# CM_CLK.net
KiCad netlist of a schematic drawn in Altium Designer
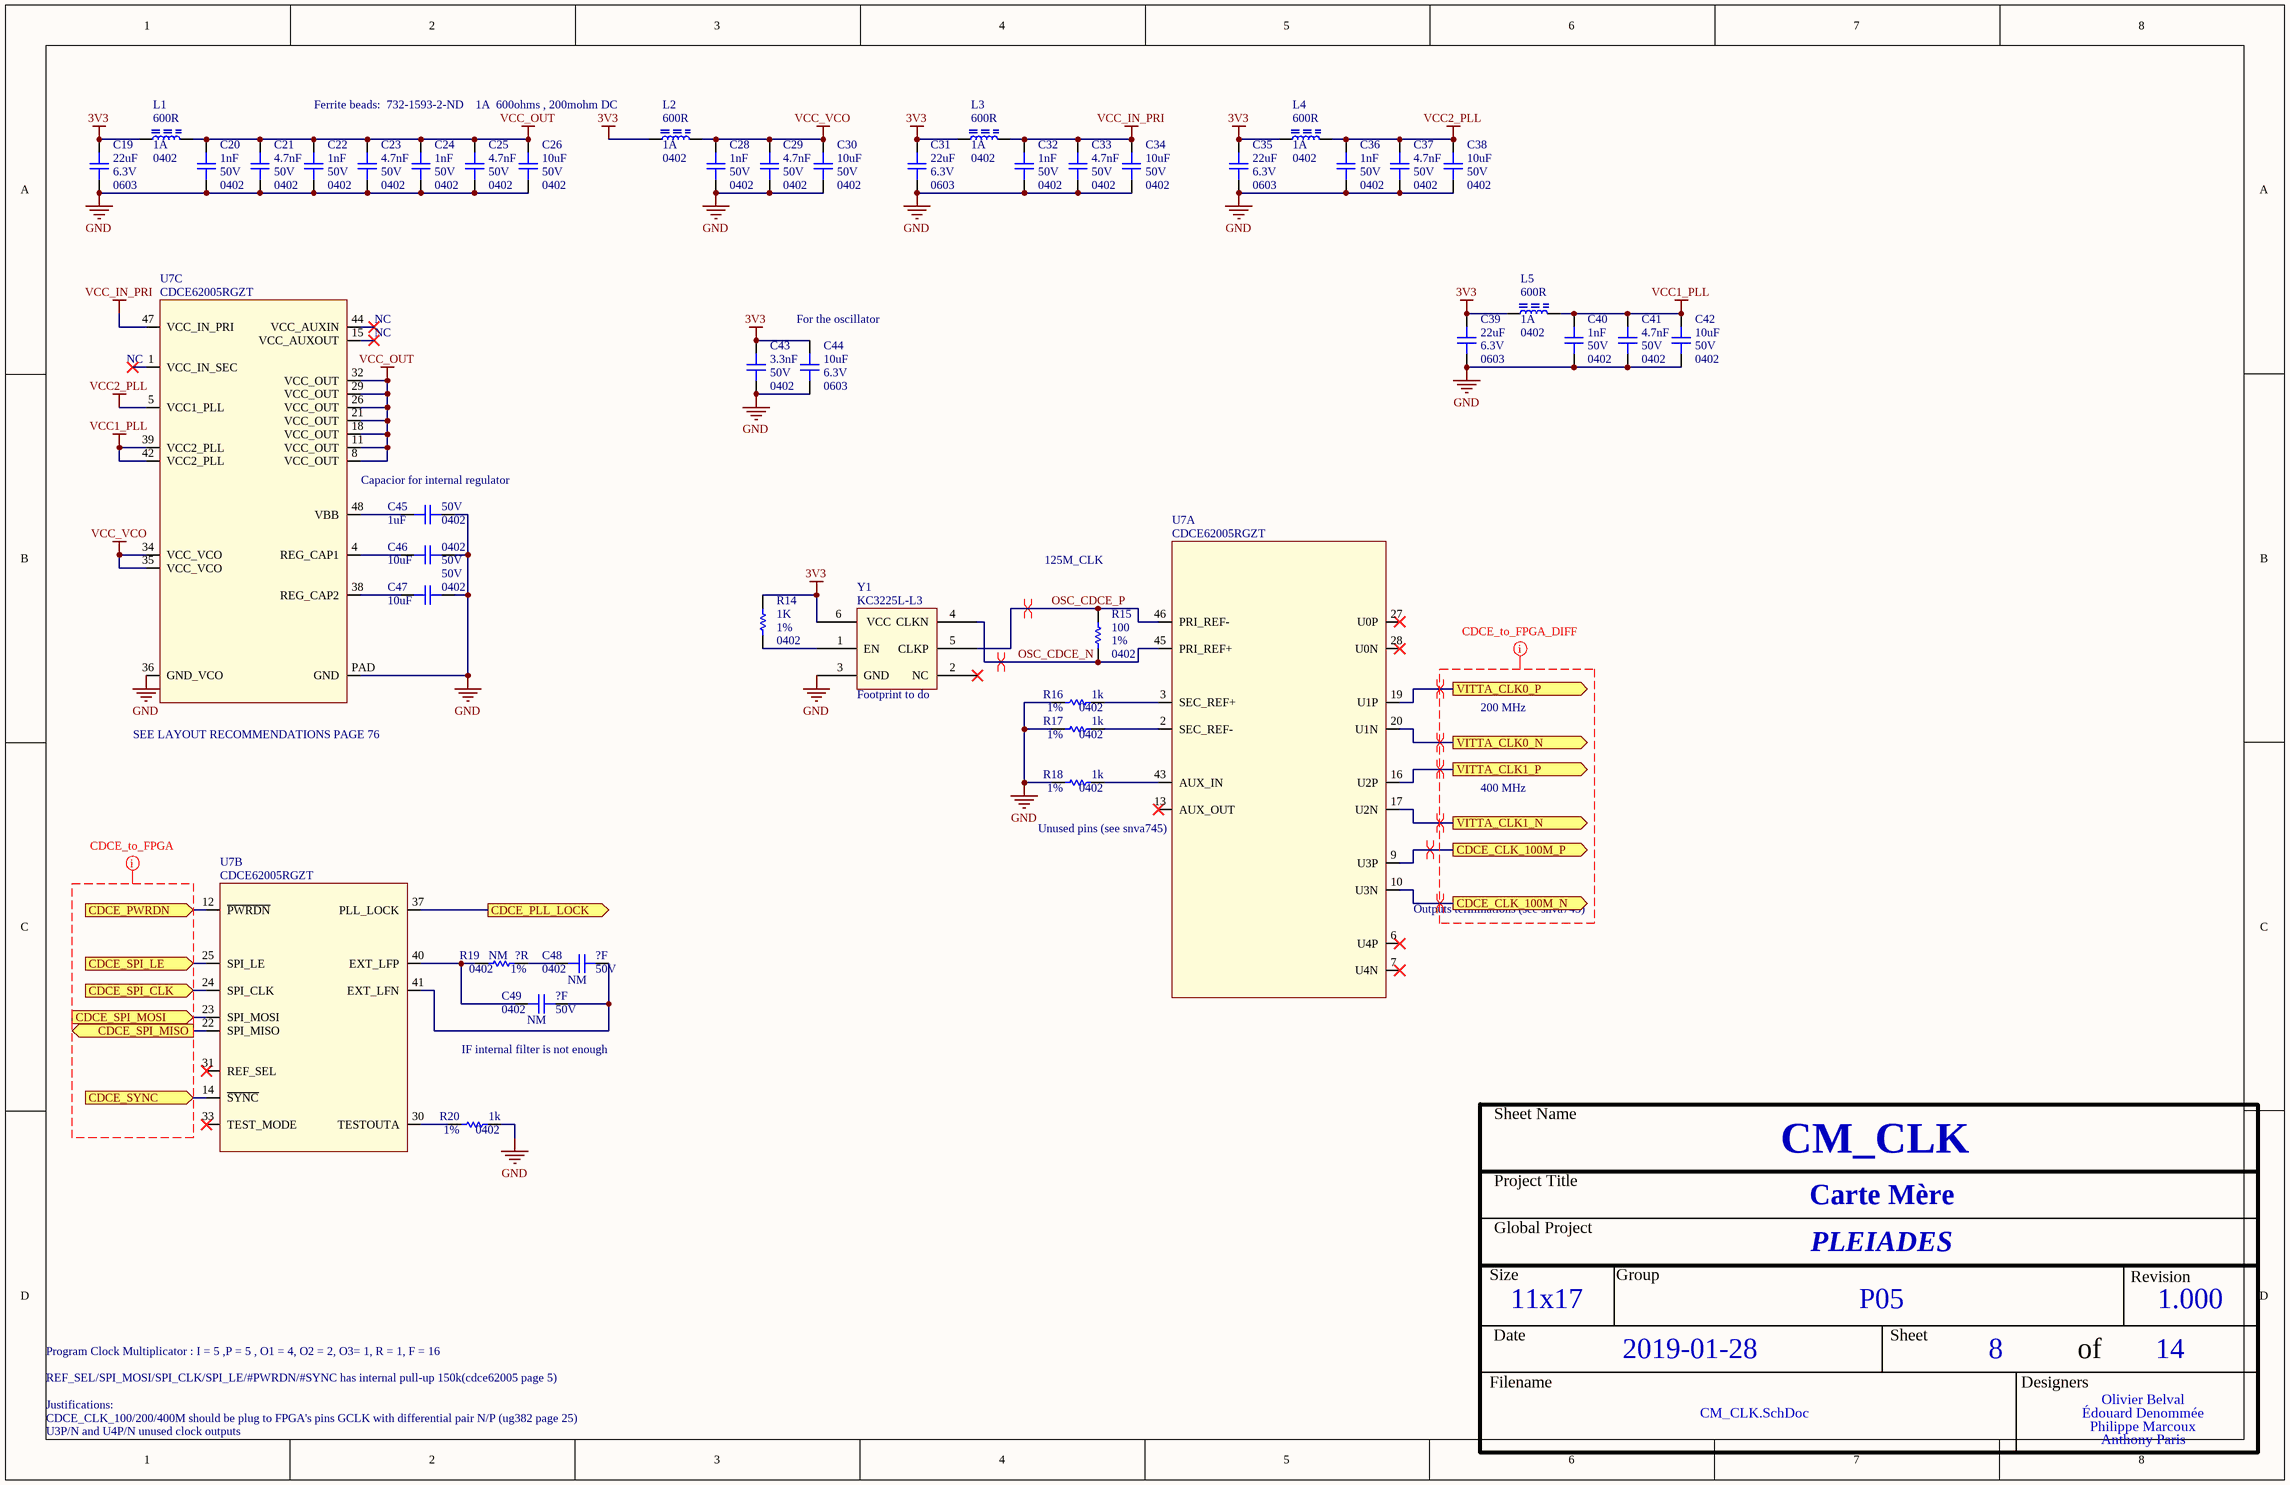
[diagram p0: CM_CLK.SchDoc]

(export (version "E")
  (design (tool "Eeschema 10.0.6"))
  (components
    (comp (ref "C19")
      (value "22uF")
      (footprint "CAP_0603")
      (description "CAP - 0603")
      (fields
        (field (name "VOLTAGE") "6.3V")
        (field (name "PACKAGE") "0603")
        (field (name "CREATEDBY") "Jonathan Bouchard")
      )
      (libsource (lib "S7CAS_Lib2019_REV1_00") (part "CAP - 0603"))
    )
    (comp (ref "C20")
      (value "1nF")
      (footprint "CAP_0402")
      (description "CAP - 0402")
      (fields
        (field (name "VOLTAGE") "50V")
        (field (name "PACKAGE") "0402")
        (field (name "CREATEDBY") "Jonathan Bouchard")
      )
      (libsource (lib "S7CAS_Lib2019_REV1_00") (part "CAP - 0402"))
    )
    (comp (ref "C21")
      (value "4.7nF")
      (footprint "CAP_0402")
      (description "CAP - 0402")
      (fields
        (field (name "VOLTAGE") "50V")
        (field (name "PACKAGE") "0402")
        (field (name "CREATEDBY") "Jonathan Bouchard")
      )
      (libsource (lib "S7CAS_Lib2019_REV1_00") (part "CAP - 0402"))
    )
    (comp (ref "C22")
      (value "1nF")
      (footprint "CAP_0402")
      (description "CAP - 0402")
      (fields
        (field (name "VOLTAGE") "50V")
        (field (name "PACKAGE") "0402")
        (field (name "CREATEDBY") "Jonathan Bouchard")
      )
      (libsource (lib "S7CAS_Lib2019_REV1_00") (part "CAP - 0402"))
    )
    (comp (ref "C23")
      (value "4.7nF")
      (footprint "CAP_0402")
      (description "CAP - 0402")
      (fields
        (field (name "VOLTAGE") "50V")
        (field (name "PACKAGE") "0402")
        (field (name "CREATEDBY") "Jonathan Bouchard")
      )
      (libsource (lib "S7CAS_Lib2019_REV1_00") (part "CAP - 0402"))
    )
    (comp (ref "C24")
      (value "1nF")
      (footprint "CAP_0402")
      (description "CAP - 0402")
      (fields
        (field (name "VOLTAGE") "50V")
        (field (name "PACKAGE") "0402")
        (field (name "CREATEDBY") "Jonathan Bouchard")
      )
      (libsource (lib "S7CAS_Lib2019_REV1_00") (part "CAP - 0402"))
    )
    (comp (ref "C25")
      (value "4.7nF")
      (footprint "CAP_0402")
      (description "CAP - 0402")
      (fields
        (field (name "VOLTAGE") "50V")
        (field (name "PACKAGE") "0402")
        (field (name "CREATEDBY") "Jonathan Bouchard")
      )
      (libsource (lib "S7CAS_Lib2019_REV1_00") (part "CAP - 0402"))
    )
    (comp (ref "C26")
      (value "10uF")
      (footprint "CAP_0402")
      (description "CAP - 0402")
      (fields
        (field (name "VOLTAGE") "50V")
        (field (name "PACKAGE") "0402")
        (field (name "CREATEDBY") "Jonathan Bouchard")
      )
      (libsource (lib "S7CAS_Lib2019_REV1_00") (part "CAP - 0402"))
    )
    (comp (ref "C28")
      (value "1nF")
      (footprint "CAP_0402")
      (description "CAP - 0402")
      (fields
        (field (name "VOLTAGE") "50V")
        (field (name "PACKAGE") "0402")
        (field (name "CREATEDBY") "Jonathan Bouchard")
      )
      (libsource (lib "S7CAS_Lib2019_REV1_00") (part "CAP - 0402"))
    )
    (comp (ref "C29")
      (value "4.7nF")
      (footprint "CAP_0402")
      (description "CAP - 0402")
      (fields
        (field (name "VOLTAGE") "50V")
        (field (name "PACKAGE") "0402")
        (field (name "CREATEDBY") "Jonathan Bouchard")
      )
      (libsource (lib "S7CAS_Lib2019_REV1_00") (part "CAP - 0402"))
    )
    (comp (ref "C30")
      (value "10uF")
      (footprint "CAP_0402")
      (description "CAP - 0402")
      (fields
        (field (name "VOLTAGE") "50V")
        (field (name "PACKAGE") "0402")
        (field (name "CREATEDBY") "Jonathan Bouchard")
      )
      (libsource (lib "S7CAS_Lib2019_REV1_00") (part "CAP - 0402"))
    )
    (comp (ref "C31")
      (value "22uF")
      (footprint "CAP_0603")
      (description "CAP - 0603")
      (fields
        (field (name "VOLTAGE") "6.3V")
        (field (name "PACKAGE") "0603")
        (field (name "CREATEDBY") "Jonathan Bouchard")
      )
      (libsource (lib "S7CAS_Lib2019_REV1_00") (part "CAP - 0603"))
    )
    (comp (ref "C32")
      (value "1nF")
      (footprint "CAP_0402")
      (description "CAP - 0402")
      (fields
        (field (name "VOLTAGE") "50V")
        (field (name "PACKAGE") "0402")
        (field (name "CREATEDBY") "Jonathan Bouchard")
      )
      (libsource (lib "S7CAS_Lib2019_REV1_00") (part "CAP - 0402"))
    )
    (comp (ref "C33")
      (value "4.7nF")
      (footprint "CAP_0402")
      (description "CAP - 0402")
      (fields
        (field (name "VOLTAGE") "50V")
        (field (name "PACKAGE") "0402")
        (field (name "CREATEDBY") "Jonathan Bouchard")
      )
      (libsource (lib "S7CAS_Lib2019_REV1_00") (part "CAP - 0402"))
    )
    (comp (ref "C34")
      (value "10uF")
      (footprint "CAP_0402")
      (description "CAP - 0402")
      (fields
        (field (name "VOLTAGE") "50V")
        (field (name "PACKAGE") "0402")
        (field (name "CREATEDBY") "Jonathan Bouchard")
      )
      (libsource (lib "S7CAS_Lib2019_REV1_00") (part "CAP - 0402"))
    )
    (comp (ref "C35")
      (value "22uF")
      (footprint "CAP_0603")
      (description "CAP - 0603")
      (fields
        (field (name "VOLTAGE") "6.3V")
        (field (name "PACKAGE") "0603")
        (field (name "CREATEDBY") "Jonathan Bouchard")
      )
      (libsource (lib "S7CAS_Lib2019_REV1_00") (part "CAP - 0603"))
    )
    (comp (ref "C36")
      (value "1nF")
      (footprint "CAP_0402")
      (description "CAP - 0402")
      (fields
        (field (name "VOLTAGE") "50V")
        (field (name "PACKAGE") "0402")
        (field (name "CREATEDBY") "Jonathan Bouchard")
      )
      (libsource (lib "S7CAS_Lib2019_REV1_00") (part "CAP - 0402"))
    )
    (comp (ref "C37")
      (value "4.7nF")
      (footprint "CAP_0402")
      (description "CAP - 0402")
      (fields
        (field (name "VOLTAGE") "50V")
        (field (name "PACKAGE") "0402")
        (field (name "CREATEDBY") "Jonathan Bouchard")
      )
      (libsource (lib "S7CAS_Lib2019_REV1_00") (part "CAP - 0402"))
    )
    (comp (ref "C38")
      (value "10uF")
      (footprint "CAP_0402")
      (description "CAP - 0402")
      (fields
        (field (name "VOLTAGE") "50V")
        (field (name "PACKAGE") "0402")
        (field (name "CREATEDBY") "Jonathan Bouchard")
      )
      (libsource (lib "S7CAS_Lib2019_REV1_00") (part "CAP - 0402"))
    )
    (comp (ref "C39")
      (value "22uF")
      (footprint "CAP_0603")
      (description "CAP - 0603")
      (fields
        (field (name "VOLTAGE") "6.3V")
        (field (name "PACKAGE") "0603")
        (field (name "CREATEDBY") "Jonathan Bouchard")
      )
      (libsource (lib "S7CAS_Lib2019_REV1_00") (part "CAP - 0603"))
    )
    (comp (ref "C40")
      (value "1nF")
      (footprint "CAP_0402")
      (description "CAP - 0402")
      (fields
        (field (name "VOLTAGE") "50V")
        (field (name "PACKAGE") "0402")
        (field (name "CREATEDBY") "Jonathan Bouchard")
      )
      (libsource (lib "S7CAS_Lib2019_REV1_00") (part "CAP - 0402"))
    )
    (comp (ref "C41")
      (value "4.7nF")
      (footprint "CAP_0402")
      (description "CAP - 0402")
      (fields
        (field (name "VOLTAGE") "50V")
        (field (name "PACKAGE") "0402")
        (field (name "CREATEDBY") "Jonathan Bouchard")
      )
      (libsource (lib "S7CAS_Lib2019_REV1_00") (part "CAP - 0402"))
    )
    (comp (ref "C42")
      (value "10uF")
      (footprint "CAP_0402")
      (description "CAP - 0402")
      (fields
        (field (name "VOLTAGE") "50V")
        (field (name "PACKAGE") "0402")
        (field (name "CREATEDBY") "Jonathan Bouchard")
      )
      (libsource (lib "S7CAS_Lib2019_REV1_00") (part "CAP - 0402"))
    )
    (comp (ref "C43")
      (value "3.3nF")
      (footprint "CAP_0402")
      (description "CAP - 0402")
      (fields
        (field (name "VOLTAGE") "50V")
        (field (name "PACKAGE") "0402")
        (field (name "CREATEDBY") "Jonathan Bouchard")
      )
      (libsource (lib "S7CAS_Lib2019_REV1_00") (part "CAP - 0402"))
    )
    (comp (ref "C44")
      (value "10uF")
      (footprint "CAP_0603")
      (description "CAP - 0603")
      (fields
        (field (name "VOLTAGE") "6.3V")
        (field (name "PACKAGE") "0603")
        (field (name "CREATEDBY") "Jonathan Bouchard")
      )
      (libsource (lib "S7CAS_Lib2019_REV1_00") (part "CAP - 0603"))
    )
    (comp (ref "C45")
      (value "1uF")
      (footprint "CAP_0402")
      (description "CAP - 0402")
      (fields
        (field (name "VOLTAGE") "50V")
        (field (name "PACKAGE") "0402")
        (field (name "CREATEDBY") "Jonathan Bouchard")
      )
      (libsource (lib "S7CAS_Lib2019_REV1_00") (part "CAP - 0402"))
    )
    (comp (ref "C46")
      (value "10uF")
      (footprint "CAP_0402")
      (description "CAP - 0402")
      (fields
        (field (name "VOLTAGE") "50V")
        (field (name "PACKAGE") "0402")
        (field (name "CREATEDBY") "Jonathan Bouchard")
      )
      (libsource (lib "S7CAS_Lib2019_REV1_00") (part "CAP - 0402"))
    )
    (comp (ref "C47")
      (value "10uF")
      (footprint "CAP_0402")
      (description "CAP - 0402")
      (fields
        (field (name "VOLTAGE") "50V")
        (field (name "PACKAGE") "0402")
        (field (name "CREATEDBY") "Jonathan Bouchard")
      )
      (libsource (lib "S7CAS_Lib2019_REV1_00") (part "CAP - 0402"))
    )
    (comp (ref "C48")
      (value "NM")
      (footprint "CAP_0402")
      (description "CAP - 0402")
      (fields
        (field (name "VOLTAGE") "50V")
        (field (name "PACKAGE") "0402")
        (field (name "ALTIUM_VALUE") "?F")
        (field (name "CREATEDBY") "Jonathan Bouchard")
      )
      (libsource (lib "S7CAS_Lib2019_REV1_00") (part "CAP - 0402"))
    )
    (comp (ref "C49")
      (value "NM")
      (footprint "CAP_0402")
      (description "CAP - 0402")
      (fields
        (field (name "VOLTAGE") "50V")
        (field (name "PACKAGE") "0402")
        (field (name "ALTIUM_VALUE") "?F")
        (field (name "CREATEDBY") "Jonathan Bouchard")
      )
      (libsource (lib "S7CAS_Lib2019_REV1_00") (part "CAP - 0402"))
    )
    (comp (ref "L1")
      (value "600R")
      (footprint "FER_0402")
      (description "FER - 0402")
      (fields
        (field (name "CURRENT") "1A")
        (field (name "PACKAGE") "0402")
        (field (name "CREATEDBY") "Jonathan Bouchard")
      )
      (libsource (lib "S7CAS_Lib2019_REV1_00") (part "FER - 0402"))
    )
    (comp (ref "L2")
      (value "600R")
      (footprint "FER_0402")
      (description "FER - 0402")
      (fields
        (field (name "CURRENT") "1A")
        (field (name "PACKAGE") "0402")
        (field (name "CREATEDBY") "Jonathan Bouchard")
      )
      (libsource (lib "S7CAS_Lib2019_REV1_00") (part "FER - 0402"))
    )
    (comp (ref "L3")
      (value "600R")
      (footprint "FER_0402")
      (description "FER - 0402")
      (fields
        (field (name "CURRENT") "1A")
        (field (name "PACKAGE") "0402")
        (field (name "CREATEDBY") "Jonathan Bouchard")
      )
      (libsource (lib "S7CAS_Lib2019_REV1_00") (part "FER - 0402"))
    )
    (comp (ref "L4")
      (value "600R")
      (footprint "FER_0402")
      (description "FER - 0402")
      (fields
        (field (name "CURRENT") "1A")
        (field (name "PACKAGE") "0402")
        (field (name "CREATEDBY") "Jonathan Bouchard")
      )
      (libsource (lib "S7CAS_Lib2019_REV1_00") (part "FER - 0402"))
    )
    (comp (ref "L5")
      (value "600R")
      (footprint "FER_0402")
      (description "FER - 0402")
      (fields
        (field (name "CURRENT") "1A")
        (field (name "PACKAGE") "0402")
        (field (name "CREATEDBY") "Jonathan Bouchard")
      )
      (libsource (lib "S7CAS_Lib2019_REV1_00") (part "FER - 0402"))
    )
    (comp (ref "R14")
      (value "1K")
      (footprint "RES_0402")
      (description "RES - 0402")
      (fields
        (field (name "VOLTAGE") "50V")
        (field (name "POWER") "1/16W")
        (field (name "PACKAGE") "0402")
        (field (name "PRECISION") "1%")
        (field (name "CREATEDBY") "Jonathan Bouchard")
      )
      (libsource (lib "S7CAS_Lib2019_REV1_00") (part "RES - 0402"))
    )
    (comp (ref "R15")
      (value "100")
      (footprint "RES_0402")
      (description "RES - 0402")
      (fields
        (field (name "VOLTAGE") "50V")
        (field (name "POWER") "1/16W")
        (field (name "PACKAGE") "0402")
        (field (name "PRECISION") "1%")
        (field (name "CREATEDBY") "Jonathan Bouchard")
      )
      (libsource (lib "S7CAS_Lib2019_REV1_00") (part "RES - 0402"))
    )
    (comp (ref "R16")
      (value "1k")
      (footprint "RES_0402")
      (description "RES - 0402")
      (fields
        (field (name "VOLTAGE") "50V")
        (field (name "POWER") "1/16W")
        (field (name "PACKAGE") "0402")
        (field (name "PRECISION") "1%")
        (field (name "CREATEDBY") "Jonathan Bouchard")
      )
      (libsource (lib "S7CAS_Lib2019_REV1_00") (part "RES - 0402"))
    )
    (comp (ref "R17")
      (value "1k")
      (footprint "RES_0402")
      (description "RES - 0402")
      (fields
        (field (name "VOLTAGE") "50V")
        (field (name "POWER") "1/16W")
        (field (name "PACKAGE") "0402")
        (field (name "PRECISION") "1%")
        (field (name "CREATEDBY") "Jonathan Bouchard")
      )
      (libsource (lib "S7CAS_Lib2019_REV1_00") (part "RES - 0402"))
    )
    (comp (ref "R18")
      (value "1k")
      (footprint "RES_0402")
      (description "RES - 0402")
      (fields
        (field (name "VOLTAGE") "50V")
        (field (name "POWER") "1/16W")
        (field (name "PACKAGE") "0402")
        (field (name "PRECISION") "1%")
        (field (name "CREATEDBY") "Jonathan Bouchard")
      )
      (libsource (lib "S7CAS_Lib2019_REV1_00") (part "RES - 0402"))
    )
    (comp (ref "R19")
      (value "NM")
      (footprint "RES_0402")
      (description "RES - 0402")
      (fields
        (field (name "VOLTAGE") "50V")
        (field (name "POWER") "1/16W")
        (field (name "PACKAGE") "0402")
        (field (name "PRECISION") "1%")
        (field (name "ALTIUM_VALUE") "?R")
        (field (name "CREATEDBY") "Jonathan Bouchard")
      )
      (libsource (lib "S7CAS_Lib2019_REV1_00") (part "RES - 0402"))
    )
    (comp (ref "R20")
      (value "1k")
      (footprint "RES_0402")
      (description "RES - 0402")
      (fields
        (field (name "VOLTAGE") "50V")
        (field (name "POWER") "1/16W")
        (field (name "PACKAGE") "0402")
        (field (name "PRECISION") "1%")
        (field (name "CREATEDBY") "Jonathan Bouchard")
      )
      (libsource (lib "S7CAS_Lib2019_REV1_00") (part "RES - 0402"))
    )
    (comp (ref "U7")
      (value "CDCE62005RGZT")
      (footprint "TIM_CDCE62005RGZT")
      (description "TIM - CLK SYNTH JITTER CLEANER 3:5 - QFN-48")
      (fields
        (field (name "VOLTAGE") "3 V ~ 3.6 V")
        (field (name "MFG") "Texas Instruments")
        (field (name "CREATEDBY") "Jonathan Bouchard")
      )
      (libsource (lib "S7CAS_Lib2019_REV1_00") (part "TIM_CDCE62005RGZT"))
    )
    (comp (ref "Y1")
      (value "KC3225L-L3")
      (footprint "KC3225L-L3_FOOTPRINT:KC3225L-L3")
      (libsource (lib "CLOCK") (part "KC3225L-L3"))
    )
  )
  (nets
    (net (code "1") (name "/CDCE_CLK_100M_N") (class "Default")
      (node (ref "U7") (pin "10") (pinfunction "U3N_10") (pintype "passive"))
    )
    (net (code "2") (name "/CDCE_CLK_100M_P") (class "Default")
      (node (ref "U7") (pin "9") (pinfunction "U3P_9") (pintype "passive"))
    )
    (net (code "3") (name "/CDCE_PLL_LOCK") (class "Default")
      (node (ref "U7") (pin "37") (pinfunction "PLL_LOCK_37") (pintype "passive"))
    )
    (net (code "4") (name "/CDCE_PWRDN") (class "Default")
      (node (ref "U7") (pin "12") (pinfunction "~{PWRDN}_12") (pintype "passive"))
    )
    (net (code "5") (name "/CDCE_SPI_CLK") (class "Default")
      (node (ref "U7") (pin "24") (pinfunction "SPI_CLK_24") (pintype "passive"))
    )
    (net (code "6") (name "/CDCE_SPI_LE") (class "Default")
      (node (ref "U7") (pin "25") (pinfunction "SPI_LE_25") (pintype "passive"))
    )
    (net (code "7") (name "/CDCE_SPI_MISO") (class "Default")
      (node (ref "U7") (pin "22") (pinfunction "SPI_MISO_22") (pintype "passive"))
    )
    (net (code "8") (name "/CDCE_SPI_MOSI") (class "Default")
      (node (ref "U7") (pin "23") (pinfunction "SPI_MOSI_23") (pintype "passive"))
    )
    (net (code "9") (name "/CDCE_SYNC") (class "Default")
      (node (ref "U7") (pin "14") (pinfunction "~{SYNC}_14") (pintype "passive"))
    )
    (net (code "10") (name "/OSC_CDCE_N") (class "Default")
      (node (ref "R15") (pin "2") (pinfunction "2_2") (pintype "passive"))
      (node (ref "U7") (pin "45") (pinfunction "PRI_REF+_45") (pintype "passive"))
      (node (ref "Y1") (pin "4") (pinfunction "CLKN_4") (pintype "passive"))
    )
    (net (code "11") (name "/OSC_CDCE_P") (class "Default")
      (node (ref "R15") (pin "1") (pinfunction "1_1") (pintype "passive"))
      (node (ref "U7") (pin "46") (pinfunction "PRI_REF-_46") (pintype "passive"))
      (node (ref "Y1") (pin "5") (pinfunction "CLKP_5") (pintype "passive"))
    )
    (net (code "12") (name "/VITTA_CLK0_N") (class "Default")
      (node (ref "U7") (pin "20") (pinfunction "U1N_20") (pintype "passive"))
    )
    (net (code "13") (name "/VITTA_CLK0_P") (class "Default")
      (node (ref "U7") (pin "19") (pinfunction "U1P_19") (pintype "passive"))
    )
    (net (code "14") (name "/VITTA_CLK1_N") (class "Default")
      (node (ref "U7") (pin "17") (pinfunction "U2N_17") (pintype "passive"))
    )
    (net (code "15") (name "/VITTA_CLK1_P") (class "Default")
      (node (ref "U7") (pin "16") (pinfunction "U2P_16") (pintype "passive"))
    )
    (net (code "16") (name "3V3") (class "Default")
      (node (ref "C19") (pin "2") (pinfunction "2_2") (pintype "passive"))
      (node (ref "C31") (pin "2") (pinfunction "2_2") (pintype "passive"))
      (node (ref "C35") (pin "2") (pinfunction "2_2") (pintype "passive"))
      (node (ref "C39") (pin "2") (pinfunction "2_2") (pintype "passive"))
      (node (ref "C43") (pin "2") (pinfunction "2_2") (pintype "passive"))
      (node (ref "C44") (pin "2") (pinfunction "2_2") (pintype "passive"))
      (node (ref "L1") (pin "2") (pinfunction "2_2") (pintype "passive"))
      (node (ref "L2") (pin "2") (pinfunction "2_2") (pintype "passive"))
      (node (ref "L3") (pin "2") (pinfunction "2_2") (pintype "passive"))
      (node (ref "L4") (pin "2") (pinfunction "2_2") (pintype "passive"))
      (node (ref "L5") (pin "2") (pinfunction "2_2") (pintype "passive"))
      (node (ref "R14") (pin "1") (pinfunction "1_1") (pintype "passive"))
      (node (ref "Y1") (pin "6") (pinfunction "VCC_6") (pintype "power_in"))
    )
    (net (code "17") (name "GND") (class "Default")
      (node (ref "C19") (pin "1") (pinfunction "1_1") (pintype "passive"))
      (node (ref "C20") (pin "1") (pinfunction "1_1") (pintype "passive"))
      (node (ref "C21") (pin "1") (pinfunction "1_1") (pintype "passive"))
      (node (ref "C22") (pin "1") (pinfunction "1_1") (pintype "passive"))
      (node (ref "C23") (pin "1") (pinfunction "1_1") (pintype "passive"))
      (node (ref "C24") (pin "1") (pinfunction "1_1") (pintype "passive"))
      (node (ref "C25") (pin "1") (pinfunction "1_1") (pintype "passive"))
      (node (ref "C26") (pin "1") (pinfunction "1_1") (pintype "passive"))
      (node (ref "C28") (pin "1") (pinfunction "1_1") (pintype "passive"))
      (node (ref "C29") (pin "1") (pinfunction "1_1") (pintype "passive"))
      (node (ref "C30") (pin "1") (pinfunction "1_1") (pintype "passive"))
      (node (ref "C31") (pin "1") (pinfunction "1_1") (pintype "passive"))
      (node (ref "C32") (pin "1") (pinfunction "1_1") (pintype "passive"))
      (node (ref "C33") (pin "1") (pinfunction "1_1") (pintype "passive"))
      (node (ref "C34") (pin "1") (pinfunction "1_1") (pintype "passive"))
      (node (ref "C35") (pin "1") (pinfunction "1_1") (pintype "passive"))
      (node (ref "C36") (pin "1") (pinfunction "1_1") (pintype "passive"))
      (node (ref "C37") (pin "1") (pinfunction "1_1") (pintype "passive"))
      (node (ref "C38") (pin "1") (pinfunction "1_1") (pintype "passive"))
      (node (ref "C39") (pin "1") (pinfunction "1_1") (pintype "passive"))
      (node (ref "C40") (pin "1") (pinfunction "1_1") (pintype "passive"))
      (node (ref "C41") (pin "1") (pinfunction "1_1") (pintype "passive"))
      (node (ref "C42") (pin "1") (pinfunction "1_1") (pintype "passive"))
      (node (ref "C43") (pin "1") (pinfunction "1_1") (pintype "passive"))
      (node (ref "C44") (pin "1") (pinfunction "1_1") (pintype "passive"))
      (node (ref "C45") (pin "1") (pinfunction "1_1") (pintype "passive"))
      (node (ref "C46") (pin "1") (pinfunction "1_1") (pintype "passive"))
      (node (ref "C47") (pin "1") (pinfunction "1_1") (pintype "passive"))
      (node (ref "R16") (pin "2") (pinfunction "2_2") (pintype "passive"))
      (node (ref "R17") (pin "2") (pinfunction "2_2") (pintype "passive"))
      (node (ref "R18") (pin "2") (pinfunction "2_2") (pintype "passive"))
      (node (ref "R20") (pin "1") (pinfunction "1_1") (pintype "passive"))
      (node (ref "U7") (pin "36") (pinfunction "GND_VCO_36") (pintype "passive"))
      (node (ref "U7") (pin "PAD") (pinfunction "GND_PAD") (pintype "passive"))
      (node (ref "Y1") (pin "3") (pinfunction "GND_3") (pintype "passive"))
    )
    (net (code "18") (name "Net-(C48-Pad2)") (class "Default")
      (node (ref "C48") (pin "2") (pinfunction "2_2") (pintype "passive"))
      (node (ref "R19") (pin "1") (pinfunction "1_1") (pintype "passive"))
    )
    (net (code "19") (name "Net-(U7A-AUX_IN)") (class "Default")
      (node (ref "R18") (pin "1") (pinfunction "1_1") (pintype "passive"))
      (node (ref "U7") (pin "43") (pinfunction "AUX_IN_43") (pintype "passive"))
    )
    (net (code "20") (name "Net-(U7A-SEC_REF+)") (class "Default")
      (node (ref "R16") (pin "1") (pinfunction "1_1") (pintype "passive"))
      (node (ref "U7") (pin "3") (pinfunction "SEC_REF+_3") (pintype "passive"))
    )
    (net (code "21") (name "Net-(U7A-SEC_REF-)") (class "Default")
      (node (ref "R17") (pin "1") (pinfunction "1_1") (pintype "passive"))
      (node (ref "U7") (pin "2") (pinfunction "SEC_REF-_2") (pintype "passive"))
    )
    (net (code "22") (name "Net-(U7B-EXT_LFN)") (class "Default")
      (node (ref "C48") (pin "1") (pinfunction "1_1") (pintype "passive"))
      (node (ref "C49") (pin "1") (pinfunction "1_1") (pintype "passive"))
      (node (ref "U7") (pin "41") (pinfunction "EXT_LFN_41") (pintype "passive"))
    )
    (net (code "23") (name "Net-(U7B-EXT_LFP)") (class "Default")
      (node (ref "C49") (pin "2") (pinfunction "2_2") (pintype "passive"))
      (node (ref "R19") (pin "2") (pinfunction "2_2") (pintype "passive"))
      (node (ref "U7") (pin "40") (pinfunction "EXT_LFP_40") (pintype "passive"))
    )
    (net (code "24") (name "Net-(U7B-TESTOUTA)") (class "Default")
      (node (ref "R20") (pin "2") (pinfunction "2_2") (pintype "passive"))
      (node (ref "U7") (pin "30") (pinfunction "TESTOUTA_30") (pintype "passive"))
    )
    (net (code "25") (name "Net-(U7C-REG_CAP1)") (class "Default")
      (node (ref "C46") (pin "2") (pinfunction "2_2") (pintype "passive"))
      (node (ref "U7") (pin "4") (pinfunction "REG_CAP1_4") (pintype "passive"))
    )
    (net (code "26") (name "Net-(U7C-REG_CAP2)") (class "Default")
      (node (ref "C47") (pin "2") (pinfunction "2_2") (pintype "passive"))
      (node (ref "U7") (pin "38") (pinfunction "REG_CAP2_38") (pintype "passive"))
    )
    (net (code "27") (name "Net-(U7C-VBB)") (class "Default")
      (node (ref "C45") (pin "2") (pinfunction "2_2") (pintype "passive"))
      (node (ref "U7") (pin "48") (pinfunction "VBB_48") (pintype "passive"))
    )
    (net (code "28") (name "Net-(Y1-EN)") (class "Default")
      (node (ref "R14") (pin "2") (pinfunction "2_2") (pintype "passive"))
      (node (ref "Y1") (pin "1") (pinfunction "EN_1") (pintype "passive"))
    )
    (net (code "29") (name "VCC1_PLL") (class "Default")
      (node (ref "C40") (pin "2") (pinfunction "2_2") (pintype "passive"))
      (node (ref "C41") (pin "2") (pinfunction "2_2") (pintype "passive"))
      (node (ref "C42") (pin "2") (pinfunction "2_2") (pintype "passive"))
      (node (ref "L5") (pin "1") (pinfunction "1_1") (pintype "passive"))
      (node (ref "U7") (pin "39") (pinfunction "VCC2_PLL_39") (pintype "passive"))
      (node (ref "U7") (pin "42") (pinfunction "VCC2_PLL_42") (pintype "passive"))
    )
    (net (code "30") (name "VCC2_PLL") (class "Default")
      (node (ref "C36") (pin "2") (pinfunction "2_2") (pintype "passive"))
      (node (ref "C37") (pin "2") (pinfunction "2_2") (pintype "passive"))
      (node (ref "C38") (pin "2") (pinfunction "2_2") (pintype "passive"))
      (node (ref "L4") (pin "1") (pinfunction "1_1") (pintype "passive"))
      (node (ref "U7") (pin "5") (pinfunction "VCC1_PLL_5") (pintype "passive"))
    )
    (net (code "31") (name "VCC_IN_PRI") (class "Default")
      (node (ref "C32") (pin "2") (pinfunction "2_2") (pintype "passive"))
      (node (ref "C33") (pin "2") (pinfunction "2_2") (pintype "passive"))
      (node (ref "C34") (pin "2") (pinfunction "2_2") (pintype "passive"))
      (node (ref "L3") (pin "1") (pinfunction "1_1") (pintype "passive"))
      (node (ref "U7") (pin "47") (pinfunction "VCC_IN_PRI_47") (pintype "passive"))
    )
    (net (code "32") (name "VCC_OUT") (class "Default")
      (node (ref "C20") (pin "2") (pinfunction "2_2") (pintype "passive"))
      (node (ref "C21") (pin "2") (pinfunction "2_2") (pintype "passive"))
      (node (ref "C22") (pin "2") (pinfunction "2_2") (pintype "passive"))
      (node (ref "C23") (pin "2") (pinfunction "2_2") (pintype "passive"))
      (node (ref "C24") (pin "2") (pinfunction "2_2") (pintype "passive"))
      (node (ref "C25") (pin "2") (pinfunction "2_2") (pintype "passive"))
      (node (ref "C26") (pin "2") (pinfunction "2_2") (pintype "passive"))
      (node (ref "L1") (pin "1") (pinfunction "1_1") (pintype "passive"))
      (node (ref "U7") (pin "11") (pinfunction "VCC_OUT_11") (pintype "passive"))
      (node (ref "U7") (pin "18") (pinfunction "VCC_OUT_18") (pintype "passive"))
      (node (ref "U7") (pin "21") (pinfunction "VCC_OUT_21") (pintype "passive"))
      (node (ref "U7") (pin "26") (pinfunction "VCC_OUT_26") (pintype "passive"))
      (node (ref "U7") (pin "29") (pinfunction "VCC_OUT_29") (pintype "passive"))
      (node (ref "U7") (pin "32") (pinfunction "VCC_OUT_32") (pintype "passive"))
      (node (ref "U7") (pin "8") (pinfunction "VCC_OUT_8") (pintype "passive"))
    )
    (net (code "33") (name "VCC_VCO") (class "Default")
      (node (ref "C28") (pin "2") (pinfunction "2_2") (pintype "passive"))
      (node (ref "C29") (pin "2") (pinfunction "2_2") (pintype "passive"))
      (node (ref "C30") (pin "2") (pinfunction "2_2") (pintype "passive"))
      (node (ref "L2") (pin "1") (pinfunction "1_1") (pintype "passive"))
      (node (ref "U7") (pin "34") (pinfunction "VCC_VCO_34") (pintype "passive"))
      (node (ref "U7") (pin "35") (pinfunction "VCC_VCO_35") (pintype "passive"))
    )
    (net (code "34") (name "unconnected-(U7A-AUX_OUT-Pad13)") (class "Default")
      (node (ref "U7") (pin "13") (pinfunction "AUX_OUT_13") (pintype "passive+no_connect"))
    )
    (net (code "35") (name "unconnected-(U7A-U0N-Pad28)") (class "Default")
      (node (ref "U7") (pin "28") (pinfunction "U0N_28") (pintype "passive+no_connect"))
    )
    (net (code "36") (name "unconnected-(U7A-U0P-Pad27)") (class "Default")
      (node (ref "U7") (pin "27") (pinfunction "U0P_27") (pintype "passive+no_connect"))
    )
    (net (code "37") (name "unconnected-(U7A-U4N-Pad7)") (class "Default")
      (node (ref "U7") (pin "7") (pinfunction "U4N_7") (pintype "passive+no_connect"))
    )
    (net (code "38") (name "unconnected-(U7A-U4P-Pad6)") (class "Default")
      (node (ref "U7") (pin "6") (pinfunction "U4P_6") (pintype "passive+no_connect"))
    )
    (net (code "39") (name "unconnected-(U7B-REF_SEL-Pad31)") (class "Default")
      (node (ref "U7") (pin "31") (pinfunction "REF_SEL_31") (pintype "passive+no_connect"))
    )
    (net (code "40") (name "unconnected-(U7B-TEST_MODE-Pad33)") (class "Default")
      (node (ref "U7") (pin "33") (pinfunction "TEST_MODE_33") (pintype "passive+no_connect"))
    )
    (net (code "41") (name "unconnected-(U7C-VCC_AUXIN-Pad44)") (class "Default")
      (node (ref "U7") (pin "44") (pinfunction "VCC_AUXIN_44") (pintype "passive+no_connect"))
    )
    (net (code "42") (name "unconnected-(U7C-VCC_AUXOUT-Pad15)") (class "Default")
      (node (ref "U7") (pin "15") (pinfunction "VCC_AUXOUT_15") (pintype "passive+no_connect"))
    )
    (net (code "43") (name "unconnected-(U7C-VCC_IN_SEC-Pad1)") (class "Default")
      (node (ref "U7") (pin "1") (pinfunction "VCC_IN_SEC_1") (pintype "passive+no_connect"))
    )
    (net (code "44") (name "unconnected-(Y1-NC-Pad2)") (class "Default")
      (node (ref "Y1") (pin "2") (pinfunction "NC_2") (pintype "passive+no_connect"))
    )
  )
)
